# Regulator.net
KiCad netlist of a schematic drawn in Altium Designer
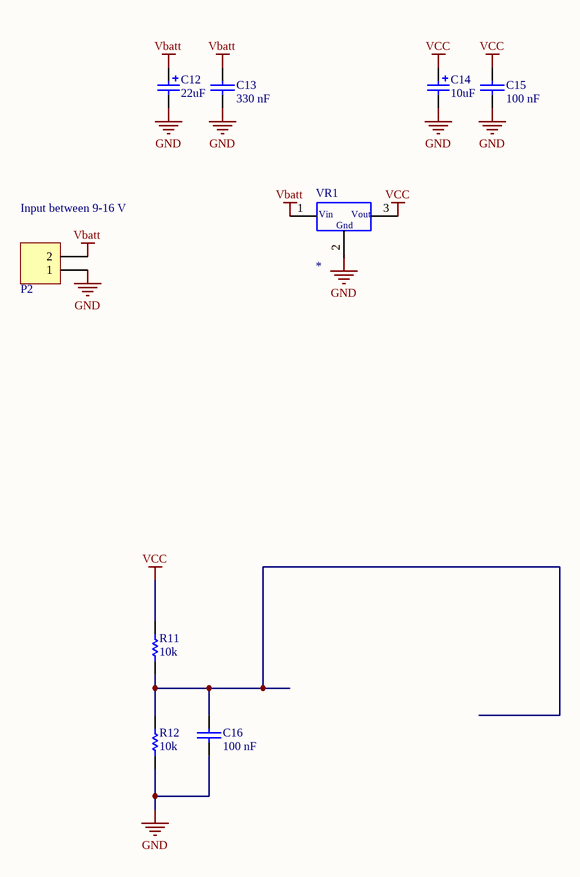
[diagram p0: Regulator.SchDoc]

(export (version "E")
  (design (tool "Eeschema 10.0.6"))
  (components
    (comp (ref "C12")
      (value "22uF")
      (footprint "ece-CAPAD2TH0.3")
      (description "Polarized Capacitor (Radial)")
      (fields (field (name "MANUFACTURER") "Generic Components") (field (name "PUBLISHER") "Altium Limited"))
      (libsource (lib "ece components") (part "CAP 22uF TH"))
    )
    (comp (ref "C13")
      (value "330 nF")
      (footprint "ece-RAD0.2")
      (description "Capacitor Non Polarised Through Hole")
      (libsource (lib "ece components") (part "CAP"))
    )
    (comp (ref "C14")
      (value "10uF")
      (footprint "ece-CAPAD2TH0.3")
      (description "Polarized Capacitor (Radial)")
      (fields (field (name "MANUFACTURER") "Generic Components") (field (name "PUBLISHER") "Altium Limited"))
      (libsource (lib "ece components") (part "CAP 22uF TH"))
    )
    (comp (ref "C15")
      (value "100 nF")
      (footprint "ece-RAD0.2")
      (description "Capacitor Non Polarised Through Hole")
      (libsource (lib "ece components") (part "CAP"))
    )
    (comp (ref "C16")
      (value "100 nF")
      (footprint "ece-RAD0.2")
      (description "Capacitor Non Polarised Through Hole")
      (libsource (lib "ece components") (part "CAP"))
    )
    (comp (ref "P2")
      (value "Connector2way")
      (footprint "ece-TER-2.02")
      (description "2 way screw connector")
      (libsource (lib "ece components") (part "Connector2way"))
    )
    (comp (ref "R11")
      (value "10k")
      (footprint "ece-AXIAL0.4")
      (description "Resistor")
      (fields (field (name "PUBLISHER") "Altium Limited"))
      (libsource (lib "ece components") (part "Res1"))
    )
    (comp (ref "R12")
      (value "10k")
      (footprint "ece-AXIAL0.4")
      (description "Resistor")
      (fields (field (name "PUBLISHER") "Altium Limited"))
      (libsource (lib "ece components") (part "Res1"))
    )
    (comp (ref "VR1")
      (value "*")
      (footprint "ece-TO220")
      (description "Voltage Regulator")
      (libsource (lib "ece components") (part "VoltRegBig"))
    )
  )
  (nets
    (net (code "1") (name "GND") (class "Default")
      (node (ref "C12") (pin "2") (pinfunction "2_2") (pintype "passive"))
      (node (ref "C13") (pin "2") (pinfunction "2_2") (pintype "passive"))
      (node (ref "C14") (pin "2") (pinfunction "2_2") (pintype "passive"))
      (node (ref "C15") (pin "2") (pinfunction "2_2") (pintype "passive"))
      (node (ref "C16") (pin "2") (pinfunction "2_2") (pintype "passive"))
      (node (ref "P2") (pin "1") (pinfunction "1_1") (pintype "passive"))
      (node (ref "R12") (pin "1") (pinfunction "1_1") (pintype "passive"))
      (node (ref "VR1") (pin "2") (pinfunction "Gnd_2") (pintype "passive"))
    )
    (net (code "2") (name "Net-(C16-Pad1)") (class "Default")
      (node (ref "C16") (pin "1") (pinfunction "1_1") (pintype "passive"))
      (node (ref "R11") (pin "1") (pinfunction "1_1") (pintype "passive"))
      (node (ref "R12") (pin "2") (pinfunction "2_2") (pintype "passive"))
    )
    (net (code "3") (name "VCC") (class "Default")
      (node (ref "C14") (pin "1") (pinfunction "1_1") (pintype "passive"))
      (node (ref "C15") (pin "1") (pinfunction "1_1") (pintype "passive"))
      (node (ref "R11") (pin "2") (pinfunction "2_2") (pintype "passive"))
      (node (ref "VR1") (pin "3") (pinfunction "Vout_3") (pintype "passive"))
    )
    (net (code "4") (name "Vbatt") (class "Default")
      (node (ref "C12") (pin "1") (pinfunction "1_1") (pintype "passive"))
      (node (ref "C13") (pin "1") (pinfunction "1_1") (pintype "passive"))
      (node (ref "P2") (pin "2") (pinfunction "2_2") (pintype "passive"))
      (node (ref "VR1") (pin "1") (pinfunction "Vin_1") (pintype "passive"))
    )
  )
)
